# ds1_redraw.net
KiCad netlist of a schematic drawn in EAGLE
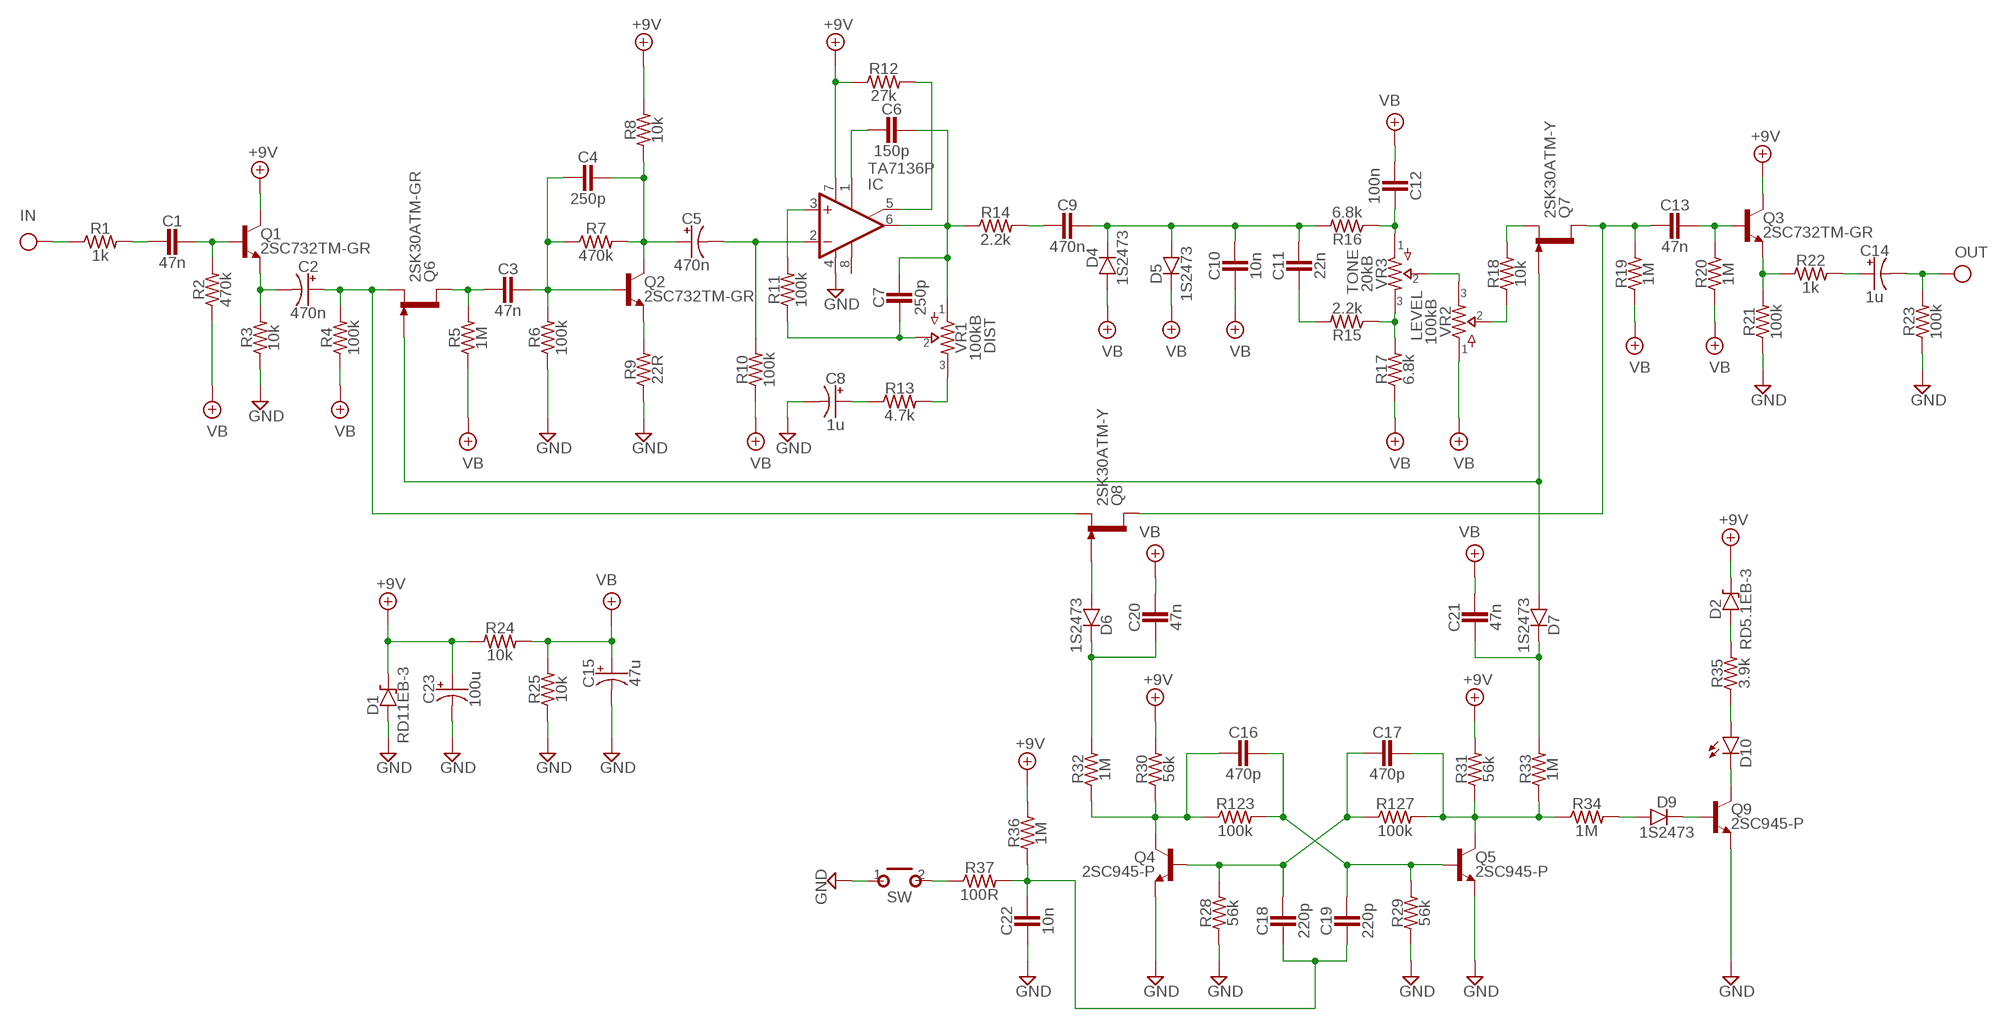
[diagram p0: schematic, sheet 1]

(export (version "E")
  (design (tool "Eeschema 10.0.6"))
  (components
    (comp (ref "C1")
      (value "47n")
      (footprint "eagle-import:BOX_SMALL")
      (libsource (lib "eagle-import") (part "CER/FILMBOX.1"))
    )
    (comp (ref "C2")
      (value "470n")
      (footprint "eagle-import:040_020")
      (libsource (lib "eagle-import") (part "0400"))
    )
    (comp (ref "C3")
      (value "47n")
      (footprint "eagle-import:BOX_SMALL")
      (libsource (lib "eagle-import") (part "CER/FILMBOX.1"))
    )
    (comp (ref "C4")
      (value "250p")
      (footprint "eagle-import:BOX_SMALL")
      (libsource (lib "eagle-import") (part "CER/FILMBOX.1"))
    )
    (comp (ref "C5")
      (value "470n")
      (footprint "eagle-import:040_020")
      (libsource (lib "eagle-import") (part "0400"))
    )
    (comp (ref "C6")
      (value "150p")
      (footprint "eagle-import:BOX_SMALL")
      (libsource (lib "eagle-import") (part "CER/FILMBOX.1"))
    )
    (comp (ref "C7")
      (value "250p")
      (footprint "eagle-import:BOX_SMALL")
      (libsource (lib "eagle-import") (part "CER/FILMBOX.1"))
    )
    (comp (ref "C8")
      (value "1u")
      (footprint "eagle-import:040_020")
      (libsource (lib "eagle-import") (part "0400"))
    )
    (comp (ref "C9")
      (value "470n")
      (footprint "eagle-import:BOX_SMALL")
      (libsource (lib "eagle-import") (part "CER/FILMBOX.1"))
    )
    (comp (ref "C10")
      (value "10n")
      (footprint "eagle-import:BOX_SMALL")
      (libsource (lib "eagle-import") (part "CER/FILMBOX.1"))
    )
    (comp (ref "C11")
      (value "22n")
      (footprint "eagle-import:BOX_SMALL")
      (libsource (lib "eagle-import") (part "CER/FILMBOX.1"))
    )
    (comp (ref "C12")
      (value "100n")
      (footprint "eagle-import:BOX_SMALL")
      (libsource (lib "eagle-import") (part "CER/FILMBOX.1"))
    )
    (comp (ref "C13")
      (value "47n")
      (footprint "eagle-import:BOX_SMALL")
      (libsource (lib "eagle-import") (part "CER/FILMBOX.1"))
    )
    (comp (ref "C14")
      (value "1u")
      (footprint "eagle-import:040_020")
      (libsource (lib "eagle-import") (part "0400"))
    )
    (comp (ref "C15")
      (value "47u")
      (footprint "eagle-import:040_020")
      (libsource (lib "eagle-import") (part "0400"))
    )
    (comp (ref "C16")
      (value "470p")
      (footprint "eagle-import:BOX_SMALL")
      (libsource (lib "eagle-import") (part "CER/FILMBOX.1"))
    )
    (comp (ref "C17")
      (value "470p")
      (footprint "eagle-import:BOX_SMALL")
      (libsource (lib "eagle-import") (part "CER/FILMBOX.1"))
    )
    (comp (ref "C18")
      (value "220p")
      (footprint "eagle-import:BOX_SMALL")
      (libsource (lib "eagle-import") (part "CER/FILMBOX.1"))
    )
    (comp (ref "C19")
      (value "220p")
      (footprint "eagle-import:BOX_SMALL")
      (libsource (lib "eagle-import") (part "CER/FILMBOX.1"))
    )
    (comp (ref "C20")
      (value "47n")
      (footprint "eagle-import:BOX_SMALL")
      (libsource (lib "eagle-import") (part "CER/FILMBOX.1"))
    )
    (comp (ref "C21")
      (value "47n")
      (footprint "eagle-import:BOX_SMALL")
      (libsource (lib "eagle-import") (part "CER/FILMBOX.1"))
    )
    (comp (ref "C22")
      (value "10n")
      (footprint "eagle-import:BOX_SMALL")
      (libsource (lib "eagle-import") (part "CER/FILMBOX.1"))
    )
    (comp (ref "C23")
      (value "100u")
      (footprint "eagle-import:040_020")
      (libsource (lib "eagle-import") (part "0400"))
    )
    (comp (ref "D1")
      (value "RD11EB-3")
      (footprint "eagle-import:DO41-2")
      (libsource (lib "eagle-import") (part "ZENER.2"))
    )
    (comp (ref "D2")
      (value "RD5.1EB-3")
      (footprint "eagle-import:DO41-2")
      (libsource (lib "eagle-import") (part "ZENER.2"))
    )
    (comp (ref "D4")
      (value "1S2473")
      (footprint "eagle-import:DO35-2")
      (libsource (lib "eagle-import") (part "DO35.2"))
    )
    (comp (ref "D5")
      (value "1S2473")
      (footprint "eagle-import:DO35-2")
      (libsource (lib "eagle-import") (part "DO35.2"))
    )
    (comp (ref "D6")
      (value "1S2473")
      (footprint "eagle-import:DO35-2")
      (libsource (lib "eagle-import") (part "DO35.2"))
    )
    (comp (ref "D7")
      (value "1S2473")
      (footprint "eagle-import:DO35-2")
      (libsource (lib "eagle-import") (part "DO35.2"))
    )
    (comp (ref "D9")
      (value "1S2473")
      (footprint "eagle-import:DO35-2")
      (libsource (lib "eagle-import") (part "DO35.2"))
    )
    (comp (ref "D10")
      (value "SLP1358")
      (footprint "eagle-import:3MM_D")
      (libsource (lib "eagle-import") (part "LED"))
    )
    (comp (ref "IC")
      (value "TA7136P")
      (footprint "eagle-import:DIL0")
      (libsource (lib "eagle-import") (part "SINGLETH"))
    )
    (comp (ref "Q1")
      (value "2SC732TM-GR")
      (footprint "eagle-import:TO92-")
      (libsource (lib "eagle-import") (part "2SC828A"))
    )
    (comp (ref "Q2")
      (value "2SC732TM-GR")
      (footprint "eagle-import:TO92-")
      (libsource (lib "eagle-import") (part "2SC828A"))
    )
    (comp (ref "Q3")
      (value "2SC732TM-GR")
      (footprint "eagle-import:TO92-")
      (libsource (lib "eagle-import") (part "2SC828A"))
    )
    (comp (ref "Q4")
      (value "2SC945-P")
      (footprint "eagle-import:TO92-")
      (libsource (lib "eagle-import") (part "2SC828A"))
    )
    (comp (ref "Q5")
      (value "2SC945-P")
      (footprint "eagle-import:TO92-")
      (libsource (lib "eagle-import") (part "2SC828A"))
    )
    (comp (ref "Q6")
      (value "2SK30ATM-GR")
      (footprint "eagle-import:TO92-")
      (libsource (lib "eagle-import") (part "2N3819TO-92S"))
    )
    (comp (ref "Q7")
      (value "2SK30ATM-Y")
      (footprint "eagle-import:TO92-")
      (libsource (lib "eagle-import") (part "2N3819TO-92S"))
    )
    (comp (ref "Q8")
      (value "2SK30ATM-Y")
      (footprint "eagle-import:TO92-")
      (libsource (lib "eagle-import") (part "2N3819TO-92S"))
    )
    (comp (ref "Q9")
      (value "2SC945-P")
      (footprint "eagle-import:TO92-")
      (libsource (lib "eagle-import") (part "2SC828A"))
    )
    (comp (ref "R1")
      (value "1k")
      (footprint "eagle-import:R0207_3")
      (libsource (lib "eagle-import") (part "R_.3B"))
    )
    (comp (ref "R2")
      (value "470k")
      (footprint "eagle-import:R0207_3")
      (libsource (lib "eagle-import") (part "R_.3B"))
    )
    (comp (ref "R3")
      (value "10k")
      (footprint "eagle-import:R0207_3")
      (libsource (lib "eagle-import") (part "R_.3B"))
    )
    (comp (ref "R4")
      (value "100k")
      (footprint "eagle-import:R0207_3")
      (libsource (lib "eagle-import") (part "R_.3B"))
    )
    (comp (ref "R5")
      (value "1M")
      (footprint "eagle-import:R0207_3")
      (libsource (lib "eagle-import") (part "R_.3B"))
    )
    (comp (ref "R6")
      (value "100k")
      (footprint "eagle-import:R0207_3")
      (libsource (lib "eagle-import") (part "R_.3B"))
    )
    (comp (ref "R7")
      (value "470k")
      (footprint "eagle-import:R0207_3")
      (libsource (lib "eagle-import") (part "R_.3B"))
    )
    (comp (ref "R8")
      (value "10k")
      (footprint "eagle-import:R0207_3")
      (libsource (lib "eagle-import") (part "R_.3B"))
    )
    (comp (ref "R9")
      (value "22R")
      (footprint "eagle-import:R0207_3")
      (libsource (lib "eagle-import") (part "R_.3B"))
    )
    (comp (ref "R10")
      (value "100k")
      (footprint "eagle-import:R0207_3")
      (libsource (lib "eagle-import") (part "R_.3B"))
    )
    (comp (ref "R11")
      (value "100k")
      (footprint "eagle-import:R0207_3")
      (libsource (lib "eagle-import") (part "R_.3B"))
    )
    (comp (ref "R12")
      (value "27k")
      (footprint "eagle-import:R0207_3")
      (libsource (lib "eagle-import") (part "R_.3B"))
    )
    (comp (ref "R13")
      (value "4.7k")
      (footprint "eagle-import:R0207_3")
      (libsource (lib "eagle-import") (part "R_.3B"))
    )
    (comp (ref "R14")
      (value "2.2k")
      (footprint "eagle-import:R0207_3")
      (libsource (lib "eagle-import") (part "R_.3B"))
    )
    (comp (ref "R15")
      (value "2.2k")
      (footprint "eagle-import:R0207_3")
      (libsource (lib "eagle-import") (part "R_.3B"))
    )
    (comp (ref "R16")
      (value "6.8k")
      (footprint "eagle-import:R0207_3")
      (libsource (lib "eagle-import") (part "R_.3B"))
    )
    (comp (ref "R17")
      (value "6.8k")
      (footprint "eagle-import:R0207_3")
      (libsource (lib "eagle-import") (part "R_.3B"))
    )
    (comp (ref "R18")
      (value "10k")
      (footprint "eagle-import:R0207_3")
      (libsource (lib "eagle-import") (part "R_.3B"))
    )
    (comp (ref "R19")
      (value "1M")
      (footprint "eagle-import:R0207_3")
      (libsource (lib "eagle-import") (part "R_.3B"))
    )
    (comp (ref "R20")
      (value "1M")
      (footprint "eagle-import:R0207_3")
      (libsource (lib "eagle-import") (part "R_.3B"))
    )
    (comp (ref "R21")
      (value "100k")
      (footprint "eagle-import:R0207_3")
      (libsource (lib "eagle-import") (part "R_.3B"))
    )
    (comp (ref "R22")
      (value "1k")
      (footprint "eagle-import:R0207_3")
      (libsource (lib "eagle-import") (part "R_.3B"))
    )
    (comp (ref "R23")
      (value "100k")
      (footprint "eagle-import:R0207_3")
      (libsource (lib "eagle-import") (part "R_.3B"))
    )
    (comp (ref "R24")
      (value "10k")
      (footprint "eagle-import:R0207_3")
      (libsource (lib "eagle-import") (part "R_.3B"))
    )
    (comp (ref "R25")
      (value "10k")
      (footprint "eagle-import:R0207_3")
      (libsource (lib "eagle-import") (part "R_.3B"))
    )
    (comp (ref "R28")
      (value "56k")
      (footprint "eagle-import:R0207_3")
      (libsource (lib "eagle-import") (part "R_.3B"))
    )
    (comp (ref "R29")
      (value "56k")
      (footprint "eagle-import:R0207_3")
      (libsource (lib "eagle-import") (part "R_.3B"))
    )
    (comp (ref "R30")
      (value "56k")
      (footprint "eagle-import:R0207_3")
      (libsource (lib "eagle-import") (part "R_.3B"))
    )
    (comp (ref "R31")
      (value "56k")
      (footprint "eagle-import:R0207_3")
      (libsource (lib "eagle-import") (part "R_.3B"))
    )
    (comp (ref "R32")
      (value "1M")
      (footprint "eagle-import:R0207_3")
      (libsource (lib "eagle-import") (part "R_.3B"))
    )
    (comp (ref "R33")
      (value "1M")
      (footprint "eagle-import:R0207_3")
      (libsource (lib "eagle-import") (part "R_.3B"))
    )
    (comp (ref "R34")
      (value "1M")
      (footprint "eagle-import:R0207_3")
      (libsource (lib "eagle-import") (part "R_.3B"))
    )
    (comp (ref "R35")
      (value "3.9k")
      (footprint "eagle-import:R0207_3")
      (libsource (lib "eagle-import") (part "R_.3B"))
    )
    (comp (ref "R36")
      (value "1M")
      (footprint "eagle-import:R0207_3")
      (libsource (lib "eagle-import") (part "R_.3B"))
    )
    (comp (ref "R37")
      (value "100R")
      (footprint "eagle-import:R0207_3")
      (libsource (lib "eagle-import") (part "R_.3B"))
    )
    (comp (ref "R123")
      (value "100k")
      (footprint "eagle-import:R0207_3")
      (libsource (lib "eagle-import") (part "R_.3B"))
    )
    (comp (ref "R127")
      (value "100k")
      (footprint "eagle-import:R0207_3")
      (libsource (lib "eagle-import") (part "R_.3B"))
    )
    (comp (ref "SW")
      (value "MOMENTARY")
      (footprint "eagle-import:SPST")
      (libsource (lib "eagle-import") (part "MOMENTARY"))
    )
    (comp (ref "VR1")
      (value "100kB")
      (footprint "eagle-import:16MM")
      (libsource (lib "eagle-import") (part "POTS16MM"))
    )
    (comp (ref "VR2")
      (value "100kB")
      (footprint "eagle-import:16MM")
      (libsource (lib "eagle-import") (part "POTS16MM"))
    )
    (comp (ref "VR3")
      (value "20kB")
      (footprint "eagle-import:16MM")
      (libsource (lib "eagle-import") (part "POTS16MM"))
    )
  )
  (nets
    (net (code "1") (name "+9V") (class "Default")
      (node (ref "C23") (pin "+") (pinfunction "+_+") (pintype "passive"))
      (node (ref "D1") (pin "C") (pinfunction "C_C") (pintype "passive"))
      (node (ref "D2") (pin "C") (pinfunction "C_C") (pintype "passive"))
      (node (ref "IC") (pin "7") (pinfunction "V+_7") (pintype "power_in"))
      (node (ref "Q1") (pin "2") (pinfunction "C_2") (pintype "passive"))
      (node (ref "Q3") (pin "2") (pinfunction "C_2") (pintype "passive"))
      (node (ref "R12") (pin "1") (pinfunction "1_1") (pintype "passive"))
      (node (ref "R24") (pin "1") (pinfunction "1_1") (pintype "passive"))
      (node (ref "R30") (pin "2") (pinfunction "2_2") (pintype "passive"))
      (node (ref "R31") (pin "2") (pinfunction "2_2") (pintype "passive"))
      (node (ref "R36") (pin "2") (pinfunction "2_2") (pintype "passive"))
      (node (ref "R8") (pin "2") (pinfunction "2_2") (pintype "passive"))
    )
    (net (code "2") (name "GND") (class "Default")
      (node (ref "C15") (pin "-") (pinfunction "-_-") (pintype "passive"))
      (node (ref "C22") (pin "2") (pinfunction "2_2") (pintype "passive"))
      (node (ref "C23") (pin "-") (pinfunction "-_-") (pintype "passive"))
      (node (ref "C8") (pin "-") (pinfunction "-_-") (pintype "passive"))
      (node (ref "D1") (pin "A") (pinfunction "A_A") (pintype "passive"))
      (node (ref "IC") (pin "4") (pinfunction "V-_4") (pintype "power_in"))
      (node (ref "Q4") (pin "3") (pinfunction "E_3") (pintype "passive"))
      (node (ref "Q5") (pin "3") (pinfunction "E_3") (pintype "passive"))
      (node (ref "Q9") (pin "3") (pinfunction "E_3") (pintype "passive"))
      (node (ref "R21") (pin "1") (pinfunction "1_1") (pintype "passive"))
      (node (ref "R23") (pin "1") (pinfunction "1_1") (pintype "passive"))
      (node (ref "R25") (pin "1") (pinfunction "1_1") (pintype "passive"))
      (node (ref "R28") (pin "1") (pinfunction "1_1") (pintype "passive"))
      (node (ref "R29") (pin "1") (pinfunction "1_1") (pintype "passive"))
      (node (ref "R3") (pin "1") (pinfunction "1_1") (pintype "passive"))
      (node (ref "R6") (pin "1") (pinfunction "1_1") (pintype "passive"))
      (node (ref "R9") (pin "1") (pinfunction "1_1") (pintype "passive"))
      (node (ref "SW") (pin "1") (pinfunction "P_1") (pintype "passive"))
    )
    (net (code "3") (name "IN") (class "Default")
      (node (ref "R1") (pin "1") (pinfunction "1_1") (pintype "passive"))
    )
    (net (code "4") (name "Net-(C1-Pad2)") (class "Default")
      (node (ref "C1") (pin "2") (pinfunction "2_2") (pintype "passive"))
      (node (ref "R1") (pin "2") (pinfunction "2_2") (pintype "passive"))
    )
    (net (code "5") (name "Net-(C7-Pad2)") (class "Default")
      (node (ref "C7") (pin "2") (pinfunction "2_2") (pintype "passive"))
      (node (ref "R11") (pin "1") (pinfunction "1_1") (pintype "passive"))
      (node (ref "VR1") (pin "2") (pinfunction "2_2") (pintype "passive"))
    )
    (net (code "6") (name "Net-(C8-Pad+)") (class "Default")
      (node (ref "C8") (pin "+") (pinfunction "+_+") (pintype "passive"))
      (node (ref "R13") (pin "1") (pinfunction "1_1") (pintype "passive"))
    )
    (net (code "7") (name "Net-(C9-Pad2)") (class "Default")
      (node (ref "C9") (pin "2") (pinfunction "2_2") (pintype "passive"))
      (node (ref "R14") (pin "2") (pinfunction "2_2") (pintype "passive"))
    )
    (net (code "8") (name "Net-(C10-Pad1)") (class "Default")
      (node (ref "C10") (pin "1") (pinfunction "1_1") (pintype "passive"))
      (node (ref "C11") (pin "1") (pinfunction "1_1") (pintype "passive"))
      (node (ref "C9") (pin "1") (pinfunction "1_1") (pintype "passive"))
      (node (ref "D4") (pin "C") (pinfunction "C_C") (pintype "passive"))
      (node (ref "D5") (pin "A") (pinfunction "A_A") (pintype "passive"))
      (node (ref "R16") (pin "2") (pinfunction "2_2") (pintype "passive"))
    )
    (net (code "9") (name "Net-(C11-Pad2)") (class "Default")
      (node (ref "C11") (pin "2") (pinfunction "2_2") (pintype "passive"))
      (node (ref "R15") (pin "2") (pinfunction "2_2") (pintype "passive"))
    )
    (net (code "10") (name "Net-(C12-Pad1)") (class "Default")
      (node (ref "C12") (pin "1") (pinfunction "1_1") (pintype "passive"))
      (node (ref "R16") (pin "1") (pinfunction "1_1") (pintype "passive"))
      (node (ref "VR3") (pin "1") (pinfunction "1_1") (pintype "passive"))
    )
    (net (code "11") (name "Net-(C14-Pad+)") (class "Default")
      (node (ref "C14") (pin "+") (pinfunction "+_+") (pintype "passive"))
      (node (ref "R22") (pin "2") (pinfunction "2_2") (pintype "passive"))
    )
    (net (code "12") (name "Net-(C18-Pad2)") (class "Default")
      (node (ref "C18") (pin "2") (pinfunction "2_2") (pintype "passive"))
      (node (ref "C19") (pin "2") (pinfunction "2_2") (pintype "passive"))
      (node (ref "C22") (pin "1") (pinfunction "1_1") (pintype "passive"))
      (node (ref "R36") (pin "1") (pinfunction "1_1") (pintype "passive"))
      (node (ref "R37") (pin "2") (pinfunction "2_2") (pintype "passive"))
    )
    (net (code "13") (name "Net-(C20-Pad2)") (class "Default")
      (node (ref "C20") (pin "2") (pinfunction "2_2") (pintype "passive"))
      (node (ref "D6") (pin "C") (pinfunction "C_C") (pintype "passive"))
      (node (ref "R32") (pin "2") (pinfunction "2_2") (pintype "passive"))
    )
    (net (code "14") (name "Net-(C21-Pad2)") (class "Default")
      (node (ref "C21") (pin "2") (pinfunction "2_2") (pintype "passive"))
      (node (ref "D7") (pin "C") (pinfunction "C_C") (pintype "passive"))
      (node (ref "R33") (pin "2") (pinfunction "2_2") (pintype "passive"))
    )
    (net (code "15") (name "Net-(D2-PadA)") (class "Default")
      (node (ref "D2") (pin "A") (pinfunction "A_A") (pintype "passive"))
      (node (ref "R35") (pin "2") (pinfunction "2_2") (pintype "passive"))
    )
    (net (code "16") (name "Net-(D9-PadA)") (class "Default")
      (node (ref "D9") (pin "A") (pinfunction "A_A") (pintype "passive"))
      (node (ref "R34") (pin "2") (pinfunction "2_2") (pintype "passive"))
    )
    (net (code "17") (name "Net-(D10-A)") (class "Default")
      (node (ref "D10") (pin "ANODE") (pinfunction "A_ANODE") (pintype "passive"))
      (node (ref "R35") (pin "1") (pinfunction "1_1") (pintype "passive"))
    )
    (net (code "18") (name "Net-(D10-C)") (class "Default")
      (node (ref "D10") (pin "P$1") (pinfunction "C_P$1") (pintype "passive"))
      (node (ref "Q9") (pin "2") (pinfunction "C_2") (pintype "passive"))
    )
    (net (code "19") (name "Net-(IC-+IN)") (class "Default")
      (node (ref "IC") (pin "3") (pinfunction "+IN_3") (pintype "input"))
      (node (ref "R11") (pin "2") (pinfunction "2_2") (pintype "passive"))
    )
    (net (code "20") (name "Net-(IC--IN)") (class "Default")
      (node (ref "C5") (pin "-") (pinfunction "-_-") (pintype "passive"))
      (node (ref "IC") (pin "2") (pinfunction "-IN_2") (pintype "input"))
      (node (ref "R10") (pin "2") (pinfunction "2_2") (pintype "passive"))
    )
    (net (code "21") (name "Net-(IC-ON1)") (class "Default")
      (node (ref "C6") (pin "2") (pinfunction "2_2") (pintype "passive"))
      (node (ref "IC") (pin "1") (pinfunction "ON1_1") (pintype "passive"))
    )
    (net (code "22") (name "Net-(IC-ON2)") (class "Default")
      (node (ref "IC") (pin "5") (pinfunction "ON2_5") (pintype "passive"))
      (node (ref "R12") (pin "2") (pinfunction "2_2") (pintype "passive"))
    )
    (net (code "23") (name "Net-(IC-OUT)") (class "Default")
      (node (ref "C6") (pin "1") (pinfunction "1_1") (pintype "passive"))
      (node (ref "C7") (pin "1") (pinfunction "1_1") (pintype "passive"))
      (node (ref "IC") (pin "6") (pinfunction "OUT_6") (pintype "output"))
      (node (ref "R14") (pin "1") (pinfunction "1_1") (pintype "passive"))
      (node (ref "VR1") (pin "1") (pinfunction "1_1") (pintype "passive"))
    )
    (net (code "24") (name "Net-(Q1-B)") (class "Default")
      (node (ref "C1") (pin "1") (pinfunction "1_1") (pintype "passive"))
      (node (ref "Q1") (pin "1") (pinfunction "B_1") (pintype "passive"))
      (node (ref "R2") (pin "2") (pinfunction "2_2") (pintype "passive"))
    )
    (net (code "25") (name "Net-(Q1-E)") (class "Default")
      (node (ref "C2") (pin "-") (pinfunction "-_-") (pintype "passive"))
      (node (ref "Q1") (pin "3") (pinfunction "E_3") (pintype "passive"))
      (node (ref "R3") (pin "2") (pinfunction "2_2") (pintype "passive"))
    )
    (net (code "26") (name "Net-(Q2-B)") (class "Default")
      (node (ref "C3") (pin "1") (pinfunction "1_1") (pintype "passive"))
      (node (ref "C4") (pin "2") (pinfunction "2_2") (pintype "passive"))
      (node (ref "Q2") (pin "1") (pinfunction "B_1") (pintype "passive"))
      (node (ref "R6") (pin "2") (pinfunction "2_2") (pintype "passive"))
      (node (ref "R7") (pin "1") (pinfunction "1_1") (pintype "passive"))
    )
    (net (code "27") (name "Net-(Q2-C)") (class "Default")
      (node (ref "C4") (pin "1") (pinfunction "1_1") (pintype "passive"))
      (node (ref "C5") (pin "+") (pinfunction "+_+") (pintype "passive"))
      (node (ref "Q2") (pin "2") (pinfunction "C_2") (pintype "passive"))
      (node (ref "R7") (pin "2") (pinfunction "2_2") (pintype "passive"))
      (node (ref "R8") (pin "1") (pinfunction "1_1") (pintype "passive"))
    )
    (net (code "28") (name "Net-(Q2-E)") (class "Default")
      (node (ref "Q2") (pin "3") (pinfunction "E_3") (pintype "passive"))
      (node (ref "R9") (pin "2") (pinfunction "2_2") (pintype "passive"))
    )
    (net (code "29") (name "Net-(Q3-B)") (class "Default")
      (node (ref "C13") (pin "1") (pinfunction "1_1") (pintype "passive"))
      (node (ref "Q3") (pin "1") (pinfunction "B_1") (pintype "passive"))
      (node (ref "R20") (pin "2") (pinfunction "2_2") (pintype "passive"))
    )
    (net (code "30") (name "Net-(Q3-E)") (class "Default")
      (node (ref "Q3") (pin "3") (pinfunction "E_3") (pintype "passive"))
      (node (ref "R21") (pin "2") (pinfunction "2_2") (pintype "passive"))
      (node (ref "R22") (pin "1") (pinfunction "1_1") (pintype "passive"))
    )
    (net (code "31") (name "Net-(Q4-B)") (class "Default")
      (node (ref "C17") (pin "2") (pinfunction "2_2") (pintype "passive"))
      (node (ref "C18") (pin "1") (pinfunction "1_1") (pintype "passive"))
      (node (ref "Q4") (pin "1") (pinfunction "B_1") (pintype "passive"))
      (node (ref "R127") (pin "1") (pinfunction "1_1") (pintype "passive"))
      (node (ref "R28") (pin "2") (pinfunction "2_2") (pintype "passive"))
    )
    (net (code "32") (name "Net-(Q4-C)") (class "Default")
      (node (ref "C16") (pin "2") (pinfunction "2_2") (pintype "passive"))
      (node (ref "Q4") (pin "2") (pinfunction "C_2") (pintype "passive"))
      (node (ref "R123") (pin "1") (pinfunction "1_1") (pintype "passive"))
      (node (ref "R30") (pin "1") (pinfunction "1_1") (pintype "passive"))
      (node (ref "R32") (pin "1") (pinfunction "1_1") (pintype "passive"))
    )
    (net (code "33") (name "Net-(Q5-B)") (class "Default")
      (node (ref "C16") (pin "1") (pinfunction "1_1") (pintype "passive"))
      (node (ref "C19") (pin "1") (pinfunction "1_1") (pintype "passive"))
      (node (ref "Q5") (pin "1") (pinfunction "B_1") (pintype "passive"))
      (node (ref "R123") (pin "2") (pinfunction "2_2") (pintype "passive"))
      (node (ref "R29") (pin "2") (pinfunction "2_2") (pintype "passive"))
    )
    (net (code "34") (name "Net-(Q5-C)") (class "Default")
      (node (ref "C17") (pin "1") (pinfunction "1_1") (pintype "passive"))
      (node (ref "Q5") (pin "2") (pinfunction "C_2") (pintype "passive"))
      (node (ref "R127") (pin "2") (pinfunction "2_2") (pintype "passive"))
      (node (ref "R31") (pin "1") (pinfunction "1_1") (pintype "passive"))
      (node (ref "R33") (pin "1") (pinfunction "1_1") (pintype "passive"))
      (node (ref "R34") (pin "1") (pinfunction "1_1") (pintype "passive"))
    )
    (net (code "35") (name "Net-(Q6-D)") (class "Default")
      (node (ref "C3") (pin "2") (pinfunction "2_2") (pintype "passive"))
      (node (ref "Q6") (pin "3") (pinfunction "D_3") (pintype "passive"))
      (node (ref "R5") (pin "2") (pinfunction "2_2") (pintype "passive"))
    )
    (net (code "36") (name "Net-(Q6-G)") (class "Default")
      (node (ref "D7") (pin "A") (pinfunction "A_A") (pintype "passive"))
      (node (ref "Q6") (pin "2") (pinfunction "G_2") (pintype "passive"))
      (node (ref "Q7") (pin "2") (pinfunction "G_2") (pintype "passive"))
    )
    (net (code "37") (name "Net-(Q6-S)") (class "Default")
      (node (ref "C2") (pin "+") (pinfunction "+_+") (pintype "passive"))
      (node (ref "Q6") (pin "1") (pinfunction "S_1") (pintype "passive"))
      (node (ref "Q8") (pin "1") (pinfunction "S_1") (pintype "passive"))
      (node (ref "R4") (pin "2") (pinfunction "2_2") (pintype "passive"))
    )
    (net (code "38") (name "Net-(Q7-D)") (class "Default")
      (node (ref "C13") (pin "2") (pinfunction "2_2") (pintype "passive"))
      (node (ref "Q7") (pin "3") (pinfunction "D_3") (pintype "passive"))
      (node (ref "Q8") (pin "3") (pinfunction "D_3") (pintype "passive"))
      (node (ref "R19") (pin "2") (pinfunction "2_2") (pintype "passive"))
    )
    (net (code "39") (name "Net-(Q7-S)") (class "Default")
      (node (ref "Q7") (pin "1") (pinfunction "S_1") (pintype "passive"))
      (node (ref "R18") (pin "2") (pinfunction "2_2") (pintype "passive"))
    )
    (net (code "40") (name "Net-(Q8-G)") (class "Default")
      (node (ref "D6") (pin "A") (pinfunction "A_A") (pintype "passive"))
      (node (ref "Q8") (pin "2") (pinfunction "G_2") (pintype "passive"))
    )
    (net (code "41") (name "Net-(Q9-B)") (class "Default")
      (node (ref "D9") (pin "C") (pinfunction "C_C") (pintype "passive"))
      (node (ref "Q9") (pin "1") (pinfunction "B_1") (pintype "passive"))
    )
    (net (code "42") (name "Net-(R13-Pad2)") (class "Default")
      (node (ref "R13") (pin "2") (pinfunction "2_2") (pintype "passive"))
      (node (ref "VR1") (pin "3") (pinfunction "3_3") (pintype "passive"))
    )
    (net (code "43") (name "Net-(R15-Pad1)") (class "Default")
      (node (ref "R15") (pin "1") (pinfunction "1_1") (pintype "passive"))
      (node (ref "R17") (pin "2") (pinfunction "2_2") (pintype "passive"))
      (node (ref "VR3") (pin "3") (pinfunction "3_3") (pintype "passive"))
    )
    (net (code "44") (name "Net-(R18-Pad1)") (class "Default")
      (node (ref "R18") (pin "1") (pinfunction "1_1") (pintype "passive"))
      (node (ref "VR2") (pin "2") (pinfunction "2_2") (pintype "passive"))
    )
    (net (code "45") (name "Net-(SW-S)") (class "Default")
      (node (ref "R37") (pin "1") (pinfunction "1_1") (pintype "passive"))
      (node (ref "SW") (pin "2") (pinfunction "S_2") (pintype "passive"))
    )
    (net (code "46") (name "Net-(VR2-Pad3)") (class "Default")
      (node (ref "VR2") (pin "3") (pinfunction "3_3") (pintype "passive"))
      (node (ref "VR3") (pin "2") (pinfunction "2_2") (pintype "passive"))
    )
    (net (code "47") (name "OUT") (class "Default")
      (node (ref "C14") (pin "-") (pinfunction "-_-") (pintype "passive"))
      (node (ref "R23") (pin "2") (pinfunction "2_2") (pintype "passive"))
    )
    (net (code "48") (name "VB") (class "Default")
      (node (ref "C10") (pin "2") (pinfunction "2_2") (pintype "passive"))
      (node (ref "C12") (pin "2") (pinfunction "2_2") (pintype "passive"))
      (node (ref "C15") (pin "+") (pinfunction "+_+") (pintype "passive"))
      (node (ref "C20") (pin "1") (pinfunction "1_1") (pintype "passive"))
      (node (ref "C21") (pin "1") (pinfunction "1_1") (pintype "passive"))
      (node (ref "D4") (pin "A") (pinfunction "A_A") (pintype "passive"))
      (node (ref "D5") (pin "C") (pinfunction "C_C") (pintype "passive"))
      (node (ref "R10") (pin "1") (pinfunction "1_1") (pintype "passive"))
      (node (ref "R17") (pin "1") (pinfunction "1_1") (pintype "passive"))
      (node (ref "R19") (pin "1") (pinfunction "1_1") (pintype "passive"))
      (node (ref "R2") (pin "1") (pinfunction "1_1") (pintype "passive"))
      (node (ref "R20") (pin "1") (pinfunction "1_1") (pintype "passive"))
      (node (ref "R24") (pin "2") (pinfunction "2_2") (pintype "passive"))
      (node (ref "R25") (pin "2") (pinfunction "2_2") (pintype "passive"))
      (node (ref "R4") (pin "1") (pinfunction "1_1") (pintype "passive"))
      (node (ref "R5") (pin "1") (pinfunction "1_1") (pintype "passive"))
      (node (ref "VR2") (pin "1") (pinfunction "1_1") (pintype "passive"))
    )
    (net (code "49") (name "unconnected-(IC-OPT-Pad8)") (class "Default")
      (node (ref "IC") (pin "8") (pinfunction "OPT_8") (pintype "passive"))
    )
  )
)
